# led_driver.net
KiCad netlist of a schematic drawn in EAGLE
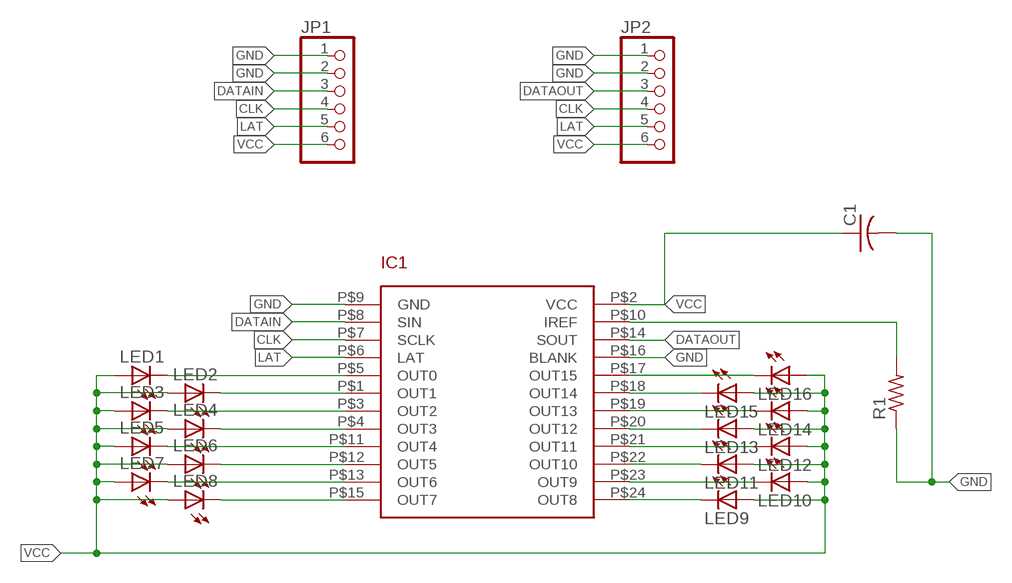
[diagram p0: schematic, sheet 1]

(export (version "E")
  (design (tool "Eeschema 10.0.6"))
  (components
    (comp (ref "C1")
      (value "C-USC1206")
      (footprint "eagle-import:C1206")
      (libsource (lib "eagle-import") (part "C-USC1206"))
    )
    (comp (ref "IC1")
      (value "TLC59282")
      (footprint "eagle-import:SSOP-24")
      (libsource (lib "eagle-import") (part "TLC59282"))
    )
    (comp (ref "JP1")
      (value "PINHD-1X6")
      (footprint "eagle-import:1X06")
      (libsource (lib "eagle-import") (part "PINHD-1X6"))
    )
    (comp (ref "JP2")
      (value "PINHD-1X6")
      (footprint "eagle-import:1X06")
      (libsource (lib "eagle-import") (part "PINHD-1X6"))
    )
    (comp (ref "LED1")
      (value "LED3MM")
      (footprint "eagle-import:LED3MM")
      (libsource (lib "eagle-import") (part "LED3MM"))
    )
    (comp (ref "LED2")
      (value "LED3MM")
      (footprint "eagle-import:LED3MM")
      (libsource (lib "eagle-import") (part "LED3MM"))
    )
    (comp (ref "LED3")
      (value "LED3MM")
      (footprint "eagle-import:LED3MM")
      (libsource (lib "eagle-import") (part "LED3MM"))
    )
    (comp (ref "LED4")
      (value "LED3MM")
      (footprint "eagle-import:LED3MM")
      (libsource (lib "eagle-import") (part "LED3MM"))
    )
    (comp (ref "LED5")
      (value "LED3MM")
      (footprint "eagle-import:LED3MM")
      (libsource (lib "eagle-import") (part "LED3MM"))
    )
    (comp (ref "LED6")
      (value "LED3MM")
      (footprint "eagle-import:LED3MM")
      (libsource (lib "eagle-import") (part "LED3MM"))
    )
    (comp (ref "LED7")
      (value "LED3MM")
      (footprint "eagle-import:LED3MM")
      (libsource (lib "eagle-import") (part "LED3MM"))
    )
    (comp (ref "LED8")
      (value "LED3MM")
      (footprint "eagle-import:LED3MM")
      (libsource (lib "eagle-import") (part "LED3MM"))
    )
    (comp (ref "LED9")
      (value "LED3MM")
      (footprint "eagle-import:LED3MM")
      (libsource (lib "eagle-import") (part "LED3MM"))
    )
    (comp (ref "LED10")
      (value "LED3MM")
      (footprint "eagle-import:LED3MM")
      (libsource (lib "eagle-import") (part "LED3MM"))
    )
    (comp (ref "LED11")
      (value "LED3MM")
      (footprint "eagle-import:LED3MM")
      (libsource (lib "eagle-import") (part "LED3MM"))
    )
    (comp (ref "LED12")
      (value "LED3MM")
      (footprint "eagle-import:LED3MM")
      (libsource (lib "eagle-import") (part "LED3MM"))
    )
    (comp (ref "LED13")
      (value "LED3MM")
      (footprint "eagle-import:LED3MM")
      (libsource (lib "eagle-import") (part "LED3MM"))
    )
    (comp (ref "LED14")
      (value "LED3MM")
      (footprint "eagle-import:LED3MM")
      (libsource (lib "eagle-import") (part "LED3MM"))
    )
    (comp (ref "LED15")
      (value "LED3MM")
      (footprint "eagle-import:LED3MM")
      (libsource (lib "eagle-import") (part "LED3MM"))
    )
    (comp (ref "LED16")
      (value "LED3MM")
      (footprint "eagle-import:LED3MM")
      (libsource (lib "eagle-import") (part "LED3MM"))
    )
    (comp (ref "R1")
      (value "R-US_0207/10")
      (footprint "eagle-import:0207_10")
      (libsource (lib "eagle-import") (part "R-US_0207/10"))
    )
  )
  (nets
    (net (code "1") (name "CLK") (class "Default")
      (node (ref "IC1") (pin "P$7") (pinfunction "SCLK_P$7") (pintype "bidirectional"))
      (node (ref "JP1") (pin "4") (pinfunction "4_4") (pintype "passive"))
      (node (ref "JP2") (pin "4") (pinfunction "4_4") (pintype "passive"))
    )
    (net (code "2") (name "DATAIN") (class "Default")
      (node (ref "IC1") (pin "P$8") (pinfunction "SIN_P$8") (pintype "bidirectional"))
      (node (ref "JP1") (pin "3") (pinfunction "3_3") (pintype "passive"))
    )
    (net (code "3") (name "DATAOUT") (class "Default")
      (node (ref "IC1") (pin "P$14") (pinfunction "SOUT_P$14") (pintype "bidirectional"))
      (node (ref "JP2") (pin "3") (pinfunction "3_3") (pintype "passive"))
    )
    (net (code "4") (name "GND") (class "Default")
      (node (ref "C1") (pin "2") (pinfunction "2_2") (pintype "passive"))
      (node (ref "IC1") (pin "P$16") (pinfunction "BLANK_P$16") (pintype "bidirectional"))
      (node (ref "IC1") (pin "P$9") (pinfunction "GND_P$9") (pintype "bidirectional"))
      (node (ref "JP1") (pin "1") (pinfunction "1_1") (pintype "passive"))
      (node (ref "JP1") (pin "2") (pinfunction "2_2") (pintype "passive"))
      (node (ref "JP2") (pin "1") (pinfunction "1_1") (pintype "passive"))
      (node (ref "JP2") (pin "2") (pinfunction "2_2") (pintype "passive"))
      (node (ref "R1") (pin "1") (pinfunction "1_1") (pintype "passive"))
    )
    (net (code "5") (name "LAT") (class "Default")
      (node (ref "IC1") (pin "P$6") (pinfunction "LAT_P$6") (pintype "bidirectional"))
      (node (ref "JP1") (pin "5") (pinfunction "5_5") (pintype "passive"))
      (node (ref "JP2") (pin "5") (pinfunction "5_5") (pintype "passive"))
    )
    (net (code "6") (name "Net-(IC1-IREF)") (class "Default")
      (node (ref "IC1") (pin "P$10") (pinfunction "IREF_P$10") (pintype "bidirectional"))
      (node (ref "R1") (pin "2") (pinfunction "2_2") (pintype "passive"))
    )
    (net (code "7") (name "Net-(IC1-OUT0)") (class "Default")
      (node (ref "IC1") (pin "P$5") (pinfunction "OUT0_P$5") (pintype "bidirectional"))
      (node (ref "LED1") (pin "K") (pinfunction "C_K") (pintype "passive"))
    )
    (net (code "8") (name "Net-(IC1-OUT1)") (class "Default")
      (node (ref "IC1") (pin "P$1") (pinfunction "OUT1_P$1") (pintype "bidirectional"))
      (node (ref "LED2") (pin "K") (pinfunction "C_K") (pintype "passive"))
    )
    (net (code "9") (name "Net-(IC1-OUT2)") (class "Default")
      (node (ref "IC1") (pin "P$3") (pinfunction "OUT2_P$3") (pintype "bidirectional"))
      (node (ref "LED3") (pin "K") (pinfunction "C_K") (pintype "passive"))
    )
    (net (code "10") (name "Net-(IC1-OUT3)") (class "Default")
      (node (ref "IC1") (pin "P$4") (pinfunction "OUT3_P$4") (pintype "bidirectional"))
      (node (ref "LED4") (pin "K") (pinfunction "C_K") (pintype "passive"))
    )
    (net (code "11") (name "Net-(IC1-OUT4)") (class "Default")
      (node (ref "IC1") (pin "P$11") (pinfunction "OUT4_P$11") (pintype "bidirectional"))
      (node (ref "LED5") (pin "K") (pinfunction "C_K") (pintype "passive"))
    )
    (net (code "12") (name "Net-(IC1-OUT5)") (class "Default")
      (node (ref "IC1") (pin "P$12") (pinfunction "OUT5_P$12") (pintype "bidirectional"))
      (node (ref "LED6") (pin "K") (pinfunction "C_K") (pintype "passive"))
    )
    (net (code "13") (name "Net-(IC1-OUT6)") (class "Default")
      (node (ref "IC1") (pin "P$13") (pinfunction "OUT6_P$13") (pintype "bidirectional"))
      (node (ref "LED7") (pin "K") (pinfunction "C_K") (pintype "passive"))
    )
    (net (code "14") (name "Net-(IC1-OUT7)") (class "Default")
      (node (ref "IC1") (pin "P$15") (pinfunction "OUT7_P$15") (pintype "bidirectional"))
      (node (ref "LED8") (pin "K") (pinfunction "C_K") (pintype "passive"))
    )
    (net (code "15") (name "Net-(IC1-OUT8)") (class "Default")
      (node (ref "IC1") (pin "P$24") (pinfunction "OUT8_P$24") (pintype "bidirectional"))
      (node (ref "LED9") (pin "K") (pinfunction "C_K") (pintype "passive"))
    )
    (net (code "16") (name "Net-(IC1-OUT9)") (class "Default")
      (node (ref "IC1") (pin "P$23") (pinfunction "OUT9_P$23") (pintype "bidirectional"))
      (node (ref "LED10") (pin "K") (pinfunction "C_K") (pintype "passive"))
    )
    (net (code "17") (name "Net-(IC1-OUT10)") (class "Default")
      (node (ref "IC1") (pin "P$22") (pinfunction "OUT10_P$22") (pintype "bidirectional"))
      (node (ref "LED11") (pin "K") (pinfunction "C_K") (pintype "passive"))
    )
    (net (code "18") (name "Net-(IC1-OUT11)") (class "Default")
      (node (ref "IC1") (pin "P$21") (pinfunction "OUT11_P$21") (pintype "bidirectional"))
      (node (ref "LED12") (pin "K") (pinfunction "C_K") (pintype "passive"))
    )
    (net (code "19") (name "Net-(IC1-OUT12)") (class "Default")
      (node (ref "IC1") (pin "P$20") (pinfunction "OUT12_P$20") (pintype "bidirectional"))
      (node (ref "LED13") (pin "K") (pinfunction "C_K") (pintype "passive"))
    )
    (net (code "20") (name "Net-(IC1-OUT13)") (class "Default")
      (node (ref "IC1") (pin "P$19") (pinfunction "OUT13_P$19") (pintype "bidirectional"))
      (node (ref "LED14") (pin "K") (pinfunction "C_K") (pintype "passive"))
    )
    (net (code "21") (name "Net-(IC1-OUT14)") (class "Default")
      (node (ref "IC1") (pin "P$18") (pinfunction "OUT14_P$18") (pintype "bidirectional"))
      (node (ref "LED15") (pin "K") (pinfunction "C_K") (pintype "passive"))
    )
    (net (code "22") (name "Net-(IC1-OUT15)") (class "Default")
      (node (ref "IC1") (pin "P$17") (pinfunction "OUT15_P$17") (pintype "bidirectional"))
      (node (ref "LED16") (pin "K") (pinfunction "C_K") (pintype "passive"))
    )
    (net (code "23") (name "VCC") (class "Default")
      (node (ref "C1") (pin "1") (pinfunction "1_1") (pintype "passive"))
      (node (ref "IC1") (pin "P$2") (pinfunction "VCC_P$2") (pintype "bidirectional"))
      (node (ref "JP1") (pin "6") (pinfunction "6_6") (pintype "passive"))
      (node (ref "JP2") (pin "6") (pinfunction "6_6") (pintype "passive"))
      (node (ref "LED1") (pin "A") (pinfunction "A_A") (pintype "passive"))
      (node (ref "LED10") (pin "A") (pinfunction "A_A") (pintype "passive"))
      (node (ref "LED11") (pin "A") (pinfunction "A_A") (pintype "passive"))
      (node (ref "LED12") (pin "A") (pinfunction "A_A") (pintype "passive"))
      (node (ref "LED13") (pin "A") (pinfunction "A_A") (pintype "passive"))
      (node (ref "LED14") (pin "A") (pinfunction "A_A") (pintype "passive"))
      (node (ref "LED15") (pin "A") (pinfunction "A_A") (pintype "passive"))
      (node (ref "LED16") (pin "A") (pinfunction "A_A") (pintype "passive"))
      (node (ref "LED2") (pin "A") (pinfunction "A_A") (pintype "passive"))
      (node (ref "LED3") (pin "A") (pinfunction "A_A") (pintype "passive"))
      (node (ref "LED4") (pin "A") (pinfunction "A_A") (pintype "passive"))
      (node (ref "LED5") (pin "A") (pinfunction "A_A") (pintype "passive"))
      (node (ref "LED6") (pin "A") (pinfunction "A_A") (pintype "passive"))
      (node (ref "LED7") (pin "A") (pinfunction "A_A") (pintype "passive"))
      (node (ref "LED8") (pin "A") (pinfunction "A_A") (pintype "passive"))
      (node (ref "LED9") (pin "A") (pinfunction "A_A") (pintype "passive"))
    )
  )
)
